# my_board.net
KiCad netlist of a schematic drawn in EAGLE
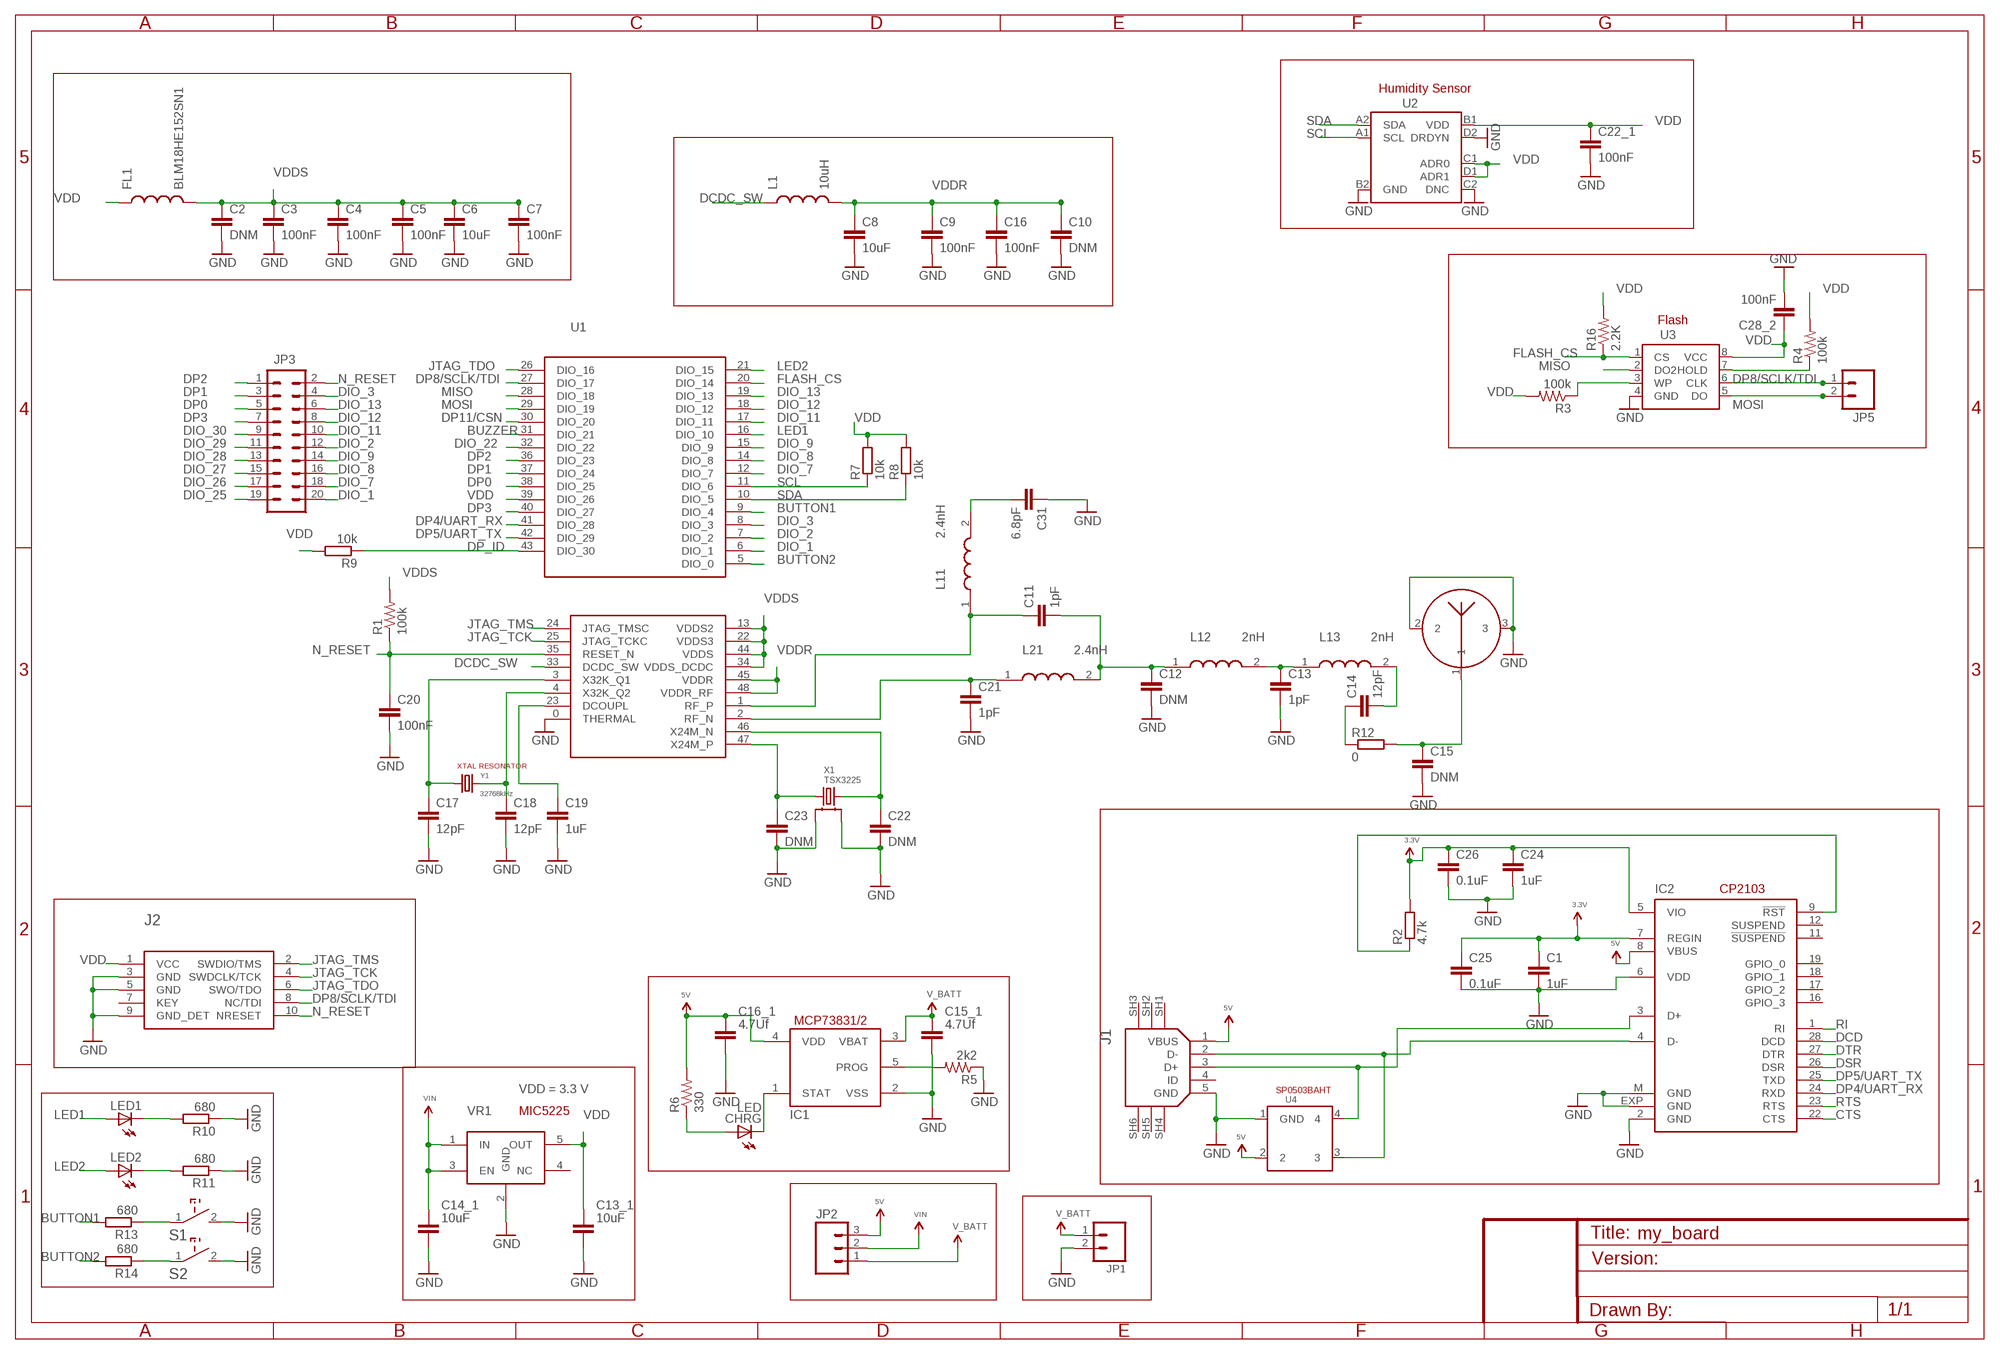
[diagram p0: schematic, sheet 1]

(export (version "E")
  (design (tool "Eeschema 10.0.6"))
  (components
    (comp (ref "C1")
      (value "1uF")
      (footprint "eagle-import:0402-CAP")
      (libsource (lib "eagle-import") (part "SparkFun-Passives_CAP0402-CAP"))
    )
    (comp (ref "C2")
      (value "DNM")
      (footprint "eagle-import:0603-CAP")
      (libsource (lib "eagle-import") (part "CAP0603-CAP"))
    )
    (comp (ref "C3")
      (value "100nF")
      (footprint "eagle-import:0402-CAP")
      (libsource (lib "eagle-import") (part "SparkFun-Passives_CAP0402-CAP"))
    )
    (comp (ref "C4")
      (value "100nF")
      (footprint "eagle-import:0402-CAP")
      (libsource (lib "eagle-import") (part "SparkFun-Passives_CAP0402-CAP"))
    )
    (comp (ref "C5")
      (value "100nF")
      (footprint "eagle-import:0402-CAP")
      (libsource (lib "eagle-import") (part "SparkFun-Passives_CAP0402-CAP"))
    )
    (comp (ref "C6")
      (value "10uF")
      (footprint "eagle-import:0603-CAP")
      (libsource (lib "eagle-import") (part "CAP0603-CAP"))
    )
    (comp (ref "C7")
      (value "100nF")
      (footprint "eagle-import:0603-CAP")
      (libsource (lib "eagle-import") (part "CAP0603-CAP"))
    )
    (comp (ref "C8")
      (value "10uF")
      (footprint "eagle-import:0603-CAP")
      (libsource (lib "eagle-import") (part "CAP0603-CAP"))
    )
    (comp (ref "C9")
      (value "100nF")
      (footprint "eagle-import:0402-CAP")
      (libsource (lib "eagle-import") (part "SparkFun-Passives_CAP0402-CAP"))
    )
    (comp (ref "C10")
      (value "DNM")
      (footprint "eagle-import:0402-CAP")
      (libsource (lib "eagle-import") (part "SparkFun-Passives_CAP0402-CAP"))
    )
    (comp (ref "C11")
      (value "1pF")
      (footprint "eagle-import:0402-CAP")
      (libsource (lib "eagle-import") (part "SparkFun-Passives_CAP0402-CAP"))
    )
    (comp (ref "C12")
      (value "DNM")
      (footprint "eagle-import:0402-CAP")
      (libsource (lib "eagle-import") (part "SparkFun-Passives_CAP0402-CAP"))
    )
    (comp (ref "C13")
      (value "1pF")
      (footprint "eagle-import:0402-CAP")
      (libsource (lib "eagle-import") (part "SparkFun-Passives_CAP0402-CAP"))
    )
    (comp (ref "C13_1")
      (value "10uF")
      (footprint "eagle-import:DP_DEVICES_C603")
      (libsource (lib "eagle-import") (part "DP_DEVICES_CAPACITOR_NPOL-0603"))
    )
    (comp (ref "C14")
      (value "12pF")
      (footprint "eagle-import:0402-CAP")
      (libsource (lib "eagle-import") (part "SparkFun-Passives_CAP0402-CAP"))
    )
    (comp (ref "C14_1")
      (value "10uF")
      (footprint "eagle-import:DP_DEVICES_C603")
      (libsource (lib "eagle-import") (part "DP_DEVICES_CAPACITOR_NPOL-0603"))
    )
    (comp (ref "C15")
      (value "DNM")
      (footprint "eagle-import:0402-CAP")
      (libsource (lib "eagle-import") (part "SparkFun-Passives_CAP0402-CAP"))
    )
    (comp (ref "C15_1")
      (value "4.7Uf")
      (footprint "eagle-import:DP_DEVICES_C603")
      (libsource (lib "eagle-import") (part "DP_DEVICES_CAPACITOR_NPOL-0603"))
    )
    (comp (ref "C16")
      (value "100nF")
      (footprint "eagle-import:0402-CAP")
      (libsource (lib "eagle-import") (part "SparkFun-Passives_CAP0402-CAP"))
    )
    (comp (ref "C16_1")
      (value "4.7Uf")
      (footprint "eagle-import:DP_DEVICES_C603")
      (libsource (lib "eagle-import") (part "DP_DEVICES_CAPACITOR_NPOL-0603"))
    )
    (comp (ref "C17")
      (value "12pF")
      (footprint "eagle-import:0402-CAP")
      (libsource (lib "eagle-import") (part "SparkFun-Passives_CAP0402-CAP"))
    )
    (comp (ref "C18")
      (value "12pF")
      (footprint "eagle-import:0402-CAP")
      (libsource (lib "eagle-import") (part "SparkFun-Passives_CAP0402-CAP"))
    )
    (comp (ref "C19")
      (value "1uF")
      (footprint "eagle-import:0402-CAP")
      (libsource (lib "eagle-import") (part "SparkFun-Passives_CAP0402-CAP"))
    )
    (comp (ref "C20")
      (value "100nF")
      (footprint "eagle-import:0402-CAP")
      (libsource (lib "eagle-import") (part "SparkFun-Passives_CAP0402-CAP"))
    )
    (comp (ref "C21")
      (value "1pF")
      (footprint "eagle-import:0402-CAP")
      (libsource (lib "eagle-import") (part "SparkFun-Passives_CAP0402-CAP"))
    )
    (comp (ref "C22")
      (value "DNM")
      (footprint "eagle-import:0402-CAP")
      (libsource (lib "eagle-import") (part "SparkFun-Passives_CAP0402-CAP"))
    )
    (comp (ref "C22_1")
      (value "100nF")
      (footprint "eagle-import:0402-CAP")
      (libsource (lib "eagle-import") (part "SparkFun-Passives_CAP0402-CAP"))
    )
    (comp (ref "C23")
      (value "DNM")
      (footprint "eagle-import:0402-CAP")
      (libsource (lib "eagle-import") (part "SparkFun-Passives_CAP0402-CAP"))
    )
    (comp (ref "C24")
      (value "1uF")
      (footprint "eagle-import:0402-CAP")
      (libsource (lib "eagle-import") (part "SparkFun-Passives_CAP0402-CAP"))
    )
    (comp (ref "C25")
      (value "0.1uF")
      (footprint "eagle-import:0402-CAP")
      (libsource (lib "eagle-import") (part "SparkFun-Passives_CAP0402-CAP"))
    )
    (comp (ref "C26")
      (value "0.1uF")
      (footprint "eagle-import:0402-CAP")
      (libsource (lib "eagle-import") (part "SparkFun-Passives_CAP0402-CAP"))
    )
    (comp (ref "C28_2")
      (value "100nF")
      (footprint "eagle-import:0402-CAP")
      (libsource (lib "eagle-import") (part "SparkFun-Passives_CAP0402-CAP"))
    )
    (comp (ref "C31")
      (value "6.8pF")
      (footprint "eagle-import:0402-CAP")
      (libsource (lib "eagle-import") (part "SparkFun-Passives_CAP0402-CAP"))
    )
    (comp (ref "CHRG")
      (value "LED")
      (footprint "eagle-import:DP_DEVICES_LED-603")
      (libsource (lib "eagle-import") (part "DP_DEVICES_LED-0603"))
    )
    (comp (ref "FL1")
      (value "BLM18HE152SN1")
      (footprint "eagle-import:0603")
      (libsource (lib "eagle-import") (part "INDUCTOR0603"))
    )
    (comp (ref "IC1")
      (value "ADAFRUIT_MCP73831/OT")
      (footprint "eagle-import:ADAFRUIT_SOT23-5L")
      (libsource (lib "eagle-import") (part "ADAFRUIT_MCP73831/OT"))
    )
    (comp (ref "IC2")
      (value "CP2103_USB_UART")
      (footprint "eagle-import:MLP28")
      (libsource (lib "eagle-import") (part "CP2103_USB_UART"))
    )
    (comp (ref "J1")
      (value "USB-1981568")
      (footprint "eagle-import:1981568-1")
      (libsource (lib "eagle-import") (part "USB-1981568"))
    )
    (comp (ref "J2")
      (value "ARM-10PIN-JTAG")
      (footprint "eagle-import:ARM-10PIN-DEBUGGER")
      (libsource (lib "eagle-import") (part "ARM-10PIN-JTAG"))
    )
    (comp (ref "JP1")
      (value "SPARKFUN-CONNECTORS_M02PTH3")
      (footprint "eagle-import:SPARKFUN-CONNECTORS_1X02_LONGPADS")
      (libsource (lib "eagle-import") (part "SPARKFUN-CONNECTORS_M02PTH3"))
    )
    (comp (ref "JP2")
      (value "M03-SCREW-5MM")
      (footprint "eagle-import:SCREWTERMINAL-5MM-3")
      (libsource (lib "eagle-import") (part "M03-SCREW-5MM"))
    )
    (comp (ref "JP3")
      (value "M10X2")
      (footprint "eagle-import:2X10")
      (libsource (lib "eagle-import") (part "M10X2"))
    )
    (comp (ref "JP5")
      (value "M02PTH")
      (footprint "eagle-import:1X02")
      (libsource (lib "eagle-import") (part "M02PTH"))
    )
    (comp (ref "L1")
      (value "10uH")
      (footprint "eagle-import:0805")
      (libsource (lib "eagle-import") (part "INDUCTOR0805"))
    )
    (comp (ref "L11")
      (value "2.4nH")
      (footprint "eagle-import:LQG15HS2N4S02D")
      (libsource (lib "eagle-import") (part "LQG15HS2N4S02D"))
    )
    (comp (ref "L12")
      (value "2nH")
      (footprint "eagle-import:LQG15HS2N4S02D")
      (libsource (lib "eagle-import") (part "LQG15HS2N4S02D"))
    )
    (comp (ref "L13")
      (value "2nH")
      (footprint "eagle-import:LQG15HS2N4S02D")
      (libsource (lib "eagle-import") (part "LQG15HS2N4S02D"))
    )
    (comp (ref "L21")
      (value "2.4nH")
      (footprint "eagle-import:LQG15HS2N4S02D")
      (libsource (lib "eagle-import") (part "LQG15HS2N4S02D"))
    )
    (comp (ref "LED1")
      (value "DP_DEVICES_LED-0805")
      (footprint "eagle-import:DP_DEVICES_LED-805")
      (libsource (lib "eagle-import") (part "DP_DEVICES_LED-0805"))
    )
    (comp (ref "LED2")
      (value "DP_DEVICES_LED-0805")
      (footprint "eagle-import:DP_DEVICES_LED-805")
      (libsource (lib "eagle-import") (part "DP_DEVICES_LED-0805"))
    )
    (comp (ref "R1")
      (value "100k")
      (footprint "eagle-import:0402-RES")
      (libsource (lib "eagle-import") (part "RESISTOR0402-RES"))
    )
    (comp (ref "R2")
      (value "4.7k")
      (footprint "eagle-import:R0402")
      (libsource (lib "eagle-import") (part "R-EU_R0402"))
    )
    (comp (ref "R3")
      (value "100k")
      (footprint "eagle-import:0402-RES")
      (libsource (lib "eagle-import") (part "RESISTOR0402-RES"))
    )
    (comp (ref "R4")
      (value "100k")
      (footprint "eagle-import:0402-RES")
      (libsource (lib "eagle-import") (part "RESISTOR0402-RES"))
    )
    (comp (ref "R5")
      (value "2k2")
      (footprint "eagle-import:SPARKFUN-RESISTORS_0805")
      (libsource (lib "eagle-import") (part "SPARKFUN-RESISTORS_RESISTOR0805-RES"))
    )
    (comp (ref "R6")
      (value "330")
      (footprint "eagle-import:SPARKFUN-RESISTORS_0805")
      (libsource (lib "eagle-import") (part "SPARKFUN-RESISTORS_RESISTOR0805-RES"))
    )
    (comp (ref "R7")
      (value "10k")
      (footprint "eagle-import:R0402")
      (libsource (lib "eagle-import") (part "R-EU_R0402"))
    )
    (comp (ref "R8")
      (value "10k")
      (footprint "eagle-import:R0402")
      (libsource (lib "eagle-import") (part "R-EU_R0402"))
    )
    (comp (ref "R9")
      (value "10k")
      (footprint "eagle-import:R0402")
      (libsource (lib "eagle-import") (part "R-EU_R0402"))
    )
    (comp (ref "R10")
      (value "680")
      (footprint "eagle-import:R0402")
      (libsource (lib "eagle-import") (part "R-EU_R0402"))
    )
    (comp (ref "R11")
      (value "680")
      (footprint "eagle-import:R0402")
      (libsource (lib "eagle-import") (part "R-EU_R0402"))
    )
    (comp (ref "R12")
      (value "0")
      (footprint "eagle-import:R0402")
      (libsource (lib "eagle-import") (part "R-EU_R0402"))
    )
    (comp (ref "R13")
      (value "680")
      (footprint "eagle-import:R0402")
      (libsource (lib "eagle-import") (part "R-EU_R0402"))
    )
    (comp (ref "R14")
      (value "680")
      (footprint "eagle-import:R0402")
      (libsource (lib "eagle-import") (part "R-EU_R0402"))
    )
    (comp (ref "R16")
      (value "2.2K")
      (footprint "eagle-import:0402-RES")
      (libsource (lib "eagle-import") (part "RESISTOR0402-RES"))
    )
    (comp (ref "S1")
      (value "B3U-1000P-SWITCH")
      (footprint "eagle-import:B3U-1000P-SWITCH")
      (libsource (lib "eagle-import") (part "B3U-1000P-SWITCH"))
    )
    (comp (ref "S2")
      (value "B3U-1000P-SWITCH")
      (footprint "eagle-import:B3U-1000P-SWITCH")
      (libsource (lib "eagle-import") (part "B3U-1000P-SWITCH"))
    )
    (comp (ref "U$1")
      (value "PCB-ANTENNA")
      (footprint "eagle-import:PCB-ANTENNA")
      (libsource (lib "eagle-import") (part "PCB-ANTENNA"))
    )
    (comp (ref "U1")
      (value "CC2650")
      (footprint "eagle-import:CC2650")
      (libsource (lib "eagle-import") (part "CC2650"))
    )
    (comp (ref "U2")
      (value "HDC1000YPA")
      (footprint "eagle-import:HDC1000YPA")
      (libsource (lib "eagle-import") (part "HDC1000YPA"))
    )
    (comp (ref "U3")
      (value "W25X40CLUXIGSS")
      (footprint "eagle-import:W25X40SSIG")
      (libsource (lib "eagle-import") (part "W25X40CLUXIGSS"))
    )
    (comp (ref "U4")
      (value "SP0503BAHT")
      (footprint "eagle-import:SP0503BAHT")
      (libsource (lib "eagle-import") (part "SP0503BAHT"))
    )
    (comp (ref "VR1")
      (value "USBUG_MIC5225-3.3YM5")
      (footprint "eagle-import:USBUG_SOT23-5")
      (fields (field (name "VOLTAGE") "3.3V"))
      (libsource (lib "eagle-import") (part "USBUG_MIC5225YM5-3.3"))
    )
    (comp (ref "X1")
      (value "TSX3225")
      (footprint "eagle-import:TSX-3225")
      (libsource (lib "eagle-import") (part "TSX-3225"))
    )
    (comp (ref "Y1")
      (value "32768kHz")
      (footprint "eagle-import:CRYSTAL_RESONATOR")
      (libsource (lib "eagle-import") (part "CRYSTAL_RESONATOR"))
    )
  )
  (nets
    (net (code "1") (name "/BUTTON1") (class "Default")
      (node (ref "R13") (pin "2") (pinfunction "2_2") (pintype "passive"))
      (node (ref "U1") (pin "9") (pinfunction "DIO_4_9") (pintype "bidirectional"))
    )
    (net (code "2") (name "/BUTTON2") (class "Default")
      (node (ref "R14") (pin "2") (pinfunction "2_2") (pintype "passive"))
      (node (ref "U1") (pin "5") (pinfunction "DIO_0_5") (pintype "bidirectional"))
    )
    (net (code "3") (name "/BUZZER") (class "Default")
      (node (ref "U1") (pin "31") (pinfunction "DIO_21_31") (pintype "bidirectional"))
    )
    (net (code "4") (name "/CTS") (class "Default")
      (node (ref "IC2") (pin "22") (pinfunction "CTS_22") (pintype "input"))
    )
    (net (code "5") (name "/DCD") (class "Default")
      (node (ref "IC2") (pin "28") (pinfunction "DCD_28") (pintype "input"))
    )
    (net (code "6") (name "/DCDC_SW") (class "Default")
      (node (ref "L1") (pin "1") (pinfunction "1_1") (pintype "passive"))
      (node (ref "U1") (pin "33") (pinfunction "DCDC_SW_33") (pintype "power_in"))
    )
    (net (code "7") (name "/DIO_1") (class "Default")
      (node (ref "JP3") (pin "20") (pinfunction "20_20") (pintype "passive"))
      (node (ref "U1") (pin "6") (pinfunction "DIO_1_6") (pintype "bidirectional"))
    )
    (net (code "8") (name "/DIO_2") (class "Default")
      (node (ref "JP3") (pin "12") (pinfunction "12_12") (pintype "passive"))
      (node (ref "U1") (pin "7") (pinfunction "DIO_2_7") (pintype "bidirectional"))
    )
    (net (code "9") (name "/DIO_3") (class "Default")
      (node (ref "JP3") (pin "4") (pinfunction "4_4") (pintype "passive"))
      (node (ref "U1") (pin "8") (pinfunction "DIO_3_8") (pintype "bidirectional"))
    )
    (net (code "10") (name "/DIO_7") (class "Default")
      (node (ref "JP3") (pin "18") (pinfunction "18_18") (pintype "passive"))
      (node (ref "U1") (pin "12") (pinfunction "DIO_7_12") (pintype "bidirectional"))
    )
    (net (code "11") (name "/DIO_8") (class "Default")
      (node (ref "JP3") (pin "16") (pinfunction "16_16") (pintype "passive"))
      (node (ref "U1") (pin "14") (pinfunction "DIO_8_14") (pintype "bidirectional"))
    )
    (net (code "12") (name "/DIO_9") (class "Default")
      (node (ref "JP3") (pin "14") (pinfunction "14_14") (pintype "passive"))
      (node (ref "U1") (pin "15") (pinfunction "DIO_9_15") (pintype "bidirectional"))
    )
    (net (code "13") (name "/DIO_11") (class "Default")
      (node (ref "JP3") (pin "10") (pinfunction "10_10") (pintype "passive"))
      (node (ref "U1") (pin "17") (pinfunction "DIO_11_17") (pintype "bidirectional"))
    )
    (net (code "14") (name "/DIO_12") (class "Default")
      (node (ref "JP3") (pin "8") (pinfunction "8_8") (pintype "passive"))
      (node (ref "U1") (pin "18") (pinfunction "DIO_12_18") (pintype "bidirectional"))
    )
    (net (code "15") (name "/DIO_13") (class "Default")
      (node (ref "JP3") (pin "6") (pinfunction "6_6") (pintype "passive"))
      (node (ref "U1") (pin "19") (pinfunction "DIO_13_19") (pintype "bidirectional"))
    )
    (net (code "16") (name "/DIO_22") (class "Default")
      (node (ref "U1") (pin "32") (pinfunction "DIO_22_32") (pintype "bidirectional"))
    )
    (net (code "17") (name "/DIO_25") (class "Default")
      (node (ref "JP3") (pin "19") (pinfunction "19_19") (pintype "passive"))
    )
    (net (code "18") (name "/DIO_26") (class "Default")
      (node (ref "JP3") (pin "17") (pinfunction "17_17") (pintype "passive"))
    )
    (net (code "19") (name "/DIO_27") (class "Default")
      (node (ref "JP3") (pin "15") (pinfunction "15_15") (pintype "passive"))
    )
    (net (code "20") (name "/DIO_28") (class "Default")
      (node (ref "JP3") (pin "13") (pinfunction "13_13") (pintype "passive"))
    )
    (net (code "21") (name "/DIO_29") (class "Default")
      (node (ref "JP3") (pin "11") (pinfunction "11_11") (pintype "passive"))
    )
    (net (code "22") (name "/DIO_30") (class "Default")
      (node (ref "JP3") (pin "9") (pinfunction "9_9") (pintype "passive"))
    )
    (net (code "23") (name "/DP0") (class "Default")
      (node (ref "JP3") (pin "5") (pinfunction "5_5") (pintype "passive"))
      (node (ref "U1") (pin "38") (pinfunction "DIO_25_38") (pintype "bidirectional"))
    )
    (net (code "24") (name "/DP1") (class "Default")
      (node (ref "JP3") (pin "3") (pinfunction "3_3") (pintype "passive"))
      (node (ref "U1") (pin "37") (pinfunction "DIO_24_37") (pintype "bidirectional"))
    )
    (net (code "25") (name "/DP2") (class "Default")
      (node (ref "JP3") (pin "1") (pinfunction "1_1") (pintype "passive"))
      (node (ref "U1") (pin "36") (pinfunction "DIO_23_36") (pintype "bidirectional"))
    )
    (net (code "26") (name "/DP3") (class "Default")
      (node (ref "JP3") (pin "7") (pinfunction "7_7") (pintype "passive"))
      (node (ref "U1") (pin "40") (pinfunction "DIO_27_40") (pintype "bidirectional"))
    )
    (net (code "27") (name "/DP4{slash}UART_RX") (class "Default")
      (node (ref "IC2") (pin "24") (pinfunction "RXD_24") (pintype "input"))
      (node (ref "U1") (pin "41") (pinfunction "DIO_28_41") (pintype "bidirectional"))
    )
    (net (code "28") (name "/DP5{slash}UART_TX") (class "Default")
      (node (ref "IC2") (pin "25") (pinfunction "TXD_25") (pintype "output"))
      (node (ref "U1") (pin "42") (pinfunction "DIO_29_42") (pintype "bidirectional"))
    )
    (net (code "29") (name "/DP8{slash}SCLK{slash}TDI") (class "Default")
      (node (ref "J2") (pin "8") (pinfunction "NC/TDI_8") (pintype "bidirectional"))
      (node (ref "JP5") (pin "1") (pinfunction "1_1") (pintype "passive"))
      (node (ref "U1") (pin "27") (pinfunction "DIO_17_27") (pintype "bidirectional"))
      (node (ref "U3") (pin "6") (pinfunction "CLK_6") (pintype "input"))
    )
    (net (code "30") (name "/DP11{slash}CSN") (class "Default")
      (node (ref "U1") (pin "30") (pinfunction "DIO_20_30") (pintype "bidirectional"))
    )
    (net (code "31") (name "/DP_ID") (class "Default")
      (node (ref "R9") (pin "1") (pinfunction "1_1") (pintype "passive"))
      (node (ref "U1") (pin "43") (pinfunction "DIO_30_43") (pintype "bidirectional"))
    )
    (net (code "32") (name "/DSR") (class "Default")
      (node (ref "IC2") (pin "26") (pinfunction "DSR_26") (pintype "input"))
    )
    (net (code "33") (name "/DTR") (class "Default")
      (node (ref "IC2") (pin "27") (pinfunction "DTR_27") (pintype "output"))
    )
    (net (code "34") (name "/FLASH_CS") (class "Default")
      (node (ref "R16") (pin "1") (pinfunction "1_1") (pintype "passive"))
      (node (ref "U1") (pin "20") (pinfunction "DIO_14_20") (pintype "bidirectional"))
      (node (ref "U3") (pin "1") (pinfunction "CS_1") (pintype "input"))
    )
    (net (code "35") (name "/JTAG_TCK") (class "Default")
      (node (ref "J2") (pin "4") (pinfunction "SWDCLK/TCK_4") (pintype "bidirectional"))
      (node (ref "U1") (pin "25") (pinfunction "JTAG_TCKC_25") (pintype "bidirectional"))
    )
    (net (code "36") (name "/JTAG_TDO") (class "Default")
      (node (ref "J2") (pin "6") (pinfunction "SWO/TDO_6") (pintype "bidirectional"))
      (node (ref "U1") (pin "26") (pinfunction "DIO_16_26") (pintype "bidirectional"))
    )
    (net (code "37") (name "/JTAG_TMS") (class "Default")
      (node (ref "J2") (pin "2") (pinfunction "SWDIO/TMS_2") (pintype "bidirectional"))
      (node (ref "U1") (pin "24") (pinfunction "JTAG_TMSC_24") (pintype "bidirectional"))
    )
    (net (code "38") (name "/LED1") (class "Default")
      (node (ref "LED1") (pin "A") (pinfunction "A_A") (pintype "passive"))
      (node (ref "U1") (pin "16") (pinfunction "DIO_10_16") (pintype "bidirectional"))
    )
    (net (code "39") (name "/LED2") (class "Default")
      (node (ref "LED2") (pin "A") (pinfunction "A_A") (pintype "passive"))
      (node (ref "U1") (pin "21") (pinfunction "DIO_15_21") (pintype "bidirectional"))
    )
    (net (code "40") (name "/MISO") (class "Default")
      (node (ref "U1") (pin "28") (pinfunction "DIO_18_28") (pintype "bidirectional"))
      (node (ref "U3") (pin "2") (pinfunction "DO2_2") (pintype "bidirectional"))
    )
    (net (code "41") (name "/MOSI") (class "Default")
      (node (ref "JP5") (pin "2") (pinfunction "2_2") (pintype "passive"))
      (node (ref "U1") (pin "29") (pinfunction "DIO_19_29") (pintype "bidirectional"))
      (node (ref "U3") (pin "5") (pinfunction "DO_5") (pintype "bidirectional"))
    )
    (net (code "42") (name "/N_RESET") (class "Default")
      (node (ref "C20") (pin "1") (pinfunction "1_1") (pintype "passive"))
      (node (ref "J2") (pin "10") (pinfunction "NRESET_10") (pintype "bidirectional"))
      (node (ref "JP3") (pin "2") (pinfunction "2_2") (pintype "passive"))
      (node (ref "R1") (pin "1") (pinfunction "1_1") (pintype "passive"))
      (node (ref "U1") (pin "35") (pinfunction "RESET_N_35") (pintype "input"))
    )
    (net (code "43") (name "/RI") (class "Default")
      (node (ref "IC2") (pin "1") (pinfunction "RI_1") (pintype "input"))
    )
    (net (code "44") (name "/RTS") (class "Default")
      (node (ref "IC2") (pin "23") (pinfunction "RTS_23") (pintype "output"))
    )
    (net (code "45") (name "/SCL") (class "Default")
      (node (ref "R7") (pin "1") (pinfunction "1_1") (pintype "passive"))
      (node (ref "U1") (pin "11") (pinfunction "DIO_6_11") (pintype "bidirectional"))
      (node (ref "U2") (pin "A1") (pinfunction "SCL_A1") (pintype "input"))
    )
    (net (code "46") (name "/SDA") (class "Default")
      (node (ref "R8") (pin "1") (pinfunction "1_1") (pintype "passive"))
      (node (ref "U1") (pin "10") (pinfunction "DIO_5_10") (pintype "bidirectional"))
      (node (ref "U2") (pin "A2") (pinfunction "SDA_A2") (pintype "bidirectional"))
    )
    (net (code "47") (name "/VDD") (class "Default")
      (node (ref "C13_1") (pin "1") (pinfunction "1_1") (pintype "passive"))
      (node (ref "C22_1") (pin "1") (pinfunction "1_1") (pintype "passive"))
      (node (ref "C28_2") (pin "1") (pinfunction "1_1") (pintype "passive"))
      (node (ref "FL1") (pin "1") (pinfunction "1_1") (pintype "passive"))
      (node (ref "J2") (pin "1") (pinfunction "VCC_1") (pintype "bidirectional"))
      (node (ref "R16") (pin "2") (pinfunction "2_2") (pintype "passive"))
      (node (ref "R3") (pin "2") (pinfunction "2_2") (pintype "passive"))
      (node (ref "R4") (pin "2") (pinfunction "2_2") (pintype "passive"))
      (node (ref "R7") (pin "2") (pinfunction "2_2") (pintype "passive"))
      (node (ref "R8") (pin "2") (pinfunction "2_2") (pintype "passive"))
      (node (ref "R9") (pin "2") (pinfunction "2_2") (pintype "passive"))
      (node (ref "U1") (pin "39") (pinfunction "DIO_26_39") (pintype "bidirectional"))
      (node (ref "U2") (pin "B1") (pinfunction "VDD_B1") (pintype "power_in"))
      (node (ref "U2") (pin "C1") (pinfunction "ADR0_C1") (pintype "input"))
      (node (ref "U2") (pin "D1") (pinfunction "ADR1_D1") (pintype "input"))
      (node (ref "U3") (pin "8") (pinfunction "VCC_8") (pintype "power_in"))
      (node (ref "VR1") (pin "5") (pinfunction "OUT_5") (pintype "passive"))
    )
    (net (code "48") (name "/VDDR") (class "Default")
      (node (ref "C10") (pin "1") (pinfunction "1_1") (pintype "passive"))
      (node (ref "C16") (pin "1") (pinfunction "1_1") (pintype "passive"))
      (node (ref "C8") (pin "1") (pinfunction "1_1") (pintype "passive"))
      (node (ref "C9") (pin "1") (pinfunction "1_1") (pintype "passive"))
      (node (ref "L1") (pin "2") (pinfunction "2_2") (pintype "passive"))
      (node (ref "U1") (pin "45") (pinfunction "VDDR_45") (pintype "power_in"))
      (node (ref "U1") (pin "48") (pinfunction "VDDR_RF_48") (pintype "power_in"))
    )
    (net (code "49") (name "/VDDS") (class "Default")
      (node (ref "C2") (pin "1") (pinfunction "1_1") (pintype "passive"))
      (node (ref "C3") (pin "1") (pinfunction "1_1") (pintype "passive"))
      (node (ref "C4") (pin "1") (pinfunction "1_1") (pintype "passive"))
      (node (ref "C5") (pin "1") (pinfunction "1_1") (pintype "passive"))
      (node (ref "C6") (pin "1") (pinfunction "1_1") (pintype "passive"))
      (node (ref "C7") (pin "1") (pinfunction "1_1") (pintype "passive"))
      (node (ref "FL1") (pin "2") (pinfunction "2_2") (pintype "passive"))
      (node (ref "R1") (pin "2") (pinfunction "2_2") (pintype "passive"))
      (node (ref "U1") (pin "13") (pinfunction "VDDS2_13") (pintype "power_in"))
      (node (ref "U1") (pin "22") (pinfunction "VDDS3_22") (pintype "power_in"))
      (node (ref "U1") (pin "34") (pinfunction "VDDS_DCDC_34") (pintype "power_in"))
      (node (ref "U1") (pin "44") (pinfunction "VDDS_44") (pintype "power_in"))
    )
    (net (code "50") (name "3.3V") (class "Default")
      (node (ref "C1") (pin "1") (pinfunction "1_1") (pintype "passive"))
      (node (ref "C24") (pin "1") (pinfunction "1_1") (pintype "passive"))
      (node (ref "C25") (pin "1") (pinfunction "1_1") (pintype "passive"))
      (node (ref "C26") (pin "1") (pinfunction "1_1") (pintype "passive"))
      (node (ref "IC2") (pin "5") (pinfunction "VIO_5") (pintype "power_in"))
      (node (ref "IC2") (pin "7") (pinfunction "REGIN_7") (pintype "passive"))
      (node (ref "R2") (pin "2") (pinfunction "2_2") (pintype "passive"))
    )
    (net (code "51") (name "5V") (class "Default")
      (node (ref "C16_1") (pin "1") (pinfunction "1_1") (pintype "passive"))
      (node (ref "IC1") (pin "4") (pinfunction "VDD_4") (pintype "power_in"))
      (node (ref "IC2") (pin "8") (pinfunction "VBUS_8") (pintype "input"))
      (node (ref "J1") (pin "1") (pinfunction "VBUS_1") (pintype "bidirectional"))
      (node (ref "JP2") (pin "3") (pinfunction "3_3") (pintype "passive"))
      (node (ref "R6") (pin "2") (pinfunction "2_2") (pintype "passive"))
      (node (ref "U4") (pin "2") (pinfunction "2_2") (pintype "bidirectional"))
    )
    (net (code "52") (name "GND") (class "Default")
      (node (ref "C1") (pin "2") (pinfunction "2_2") (pintype "passive"))
      (node (ref "C10") (pin "2") (pinfunction "2_2") (pintype "passive"))
      (node (ref "C12") (pin "2") (pinfunction "2_2") (pintype "passive"))
      (node (ref "C13") (pin "2") (pinfunction "2_2") (pintype "passive"))
      (node (ref "C13_1") (pin "2") (pinfunction "2_2") (pintype "passive"))
      (node (ref "C14_1") (pin "2") (pinfunction "2_2") (pintype "passive"))
      (node (ref "C15") (pin "2") (pinfunction "2_2") (pintype "passive"))
      (node (ref "C15_1") (pin "2") (pinfunction "2_2") (pintype "passive"))
      (node (ref "C16") (pin "2") (pinfunction "2_2") (pintype "passive"))
      (node (ref "C16_1") (pin "2") (pinfunction "2_2") (pintype "passive"))
      (node (ref "C17") (pin "2") (pinfunction "2_2") (pintype "passive"))
      (node (ref "C18") (pin "2") (pinfunction "2_2") (pintype "passive"))
      (node (ref "C19") (pin "2") (pinfunction "2_2") (pintype "passive"))
      (node (ref "C2") (pin "2") (pinfunction "2_2") (pintype "passive"))
      (node (ref "C20") (pin "2") (pinfunction "2_2") (pintype "passive"))
      (node (ref "C21") (pin "2") (pinfunction "2_2") (pintype "passive"))
      (node (ref "C22") (pin "2") (pinfunction "2_2") (pintype "passive"))
      (node (ref "C22_1") (pin "2") (pinfunction "2_2") (pintype "passive"))
      (node (ref "C23") (pin "2") (pinfunction "2_2") (pintype "passive"))
      (node (ref "C24") (pin "2") (pinfunction "2_2") (pintype "passive"))
      (node (ref "C25") (pin "2") (pinfunction "2_2") (pintype "passive"))
      (node (ref "C26") (pin "2") (pinfunction "2_2") (pintype "passive"))
      (node (ref "C28_2") (pin "2") (pinfunction "2_2") (pintype "passive"))
      (node (ref "C3") (pin "2") (pinfunction "2_2") (pintype "passive"))
      (node (ref "C31") (pin "1") (pinfunction "1_1") (pintype "passive"))
      (node (ref "C4") (pin "2") (pinfunction "2_2") (pintype "passive"))
      (node (ref "C5") (pin "2") (pinfunction "2_2") (pintype "passive"))
      (node (ref "C6") (pin "2") (pinfunction "2_2") (pintype "passive"))
      (node (ref "C7") (pin "2") (pinfunction "2_2") (pintype "passive"))
      (node (ref "C8") (pin "2") (pinfunction "2_2") (pintype "passive"))
      (node (ref "C9") (pin "2") (pinfunction "2_2") (pintype "passive"))
      (node (ref "IC1") (pin "2") (pinfunction "VSS_2") (pintype "power_in"))
      (node (ref "IC2") (pin "2") (pinfunction "GND_2") (pintype "power_in"))
      (node (ref "IC2") (pin "6") (pinfunction "VDD_6") (pintype "power_in"))
      (node (ref "IC2") (pin "EXP") (pinfunction "GND_EXP") (pintype "power_in"))
      (node (ref "IC2") (pin "M") (pinfunction "GND_M") (pintype "power_in"))
      (node (ref "J1") (pin "5") (pinfunction "GND_5") (pintype "bidirectional"))
      (node (ref "J2") (pin "3") (pinfunction "GND_3") (pintype "bidirectional"))
      (node (ref "J2") (pin "5") (pinfunction "GND_5") (pintype "bidirectional"))
      (node (ref "J2") (pin "9") (pinfunction "GND_DET_9") (pintype "bidirectional"))
      (node (ref "JP1") (pin "2") (pinfunction "2_2") (pintype "passive"))
      (node (ref "R10") (pin "1") (pinfunction "1_1") (pintype "passive"))
      (node (ref "R11") (pin "1") (pinfunction "1_1") (pintype "passive"))
      (node (ref "R5") (pin "1") (pinfunction "1_1") (pintype "passive"))
      (node (ref "S1") (pin "2") (pinfunction "2_2") (pintype "bidirectional"))
      (node (ref "S2") (pin "2") (pinfunction "2_2") (pintype "bidirectional"))
      (node (ref "U$1") (pin "2") (pinfunction "2_2") (pintype "bidirectional"))
      (node (ref "U$1") (pin "3") (pinfunction "3_3") (pintype "bidirectional"))
      (node (ref "U1") (pin "0") (pinfunction "THERMAL_0") (pintype "bidirectional"))
      (node (ref "U2") (pin "B2") (pinfunction "GND_B2") (pintype "power_in"))
      (node (ref "U2") (pin "C2") (pinfunction "DNC_C2") (pintype "power_in"))
      (node (ref "U2") (pin "D2") (pinfunction "DRDYN_D2") (pintype "bidirectional"))
      (node (ref "U3") (pin "4") (pinfunction "GND_4") (pintype "power_in"))
      (node (ref "U4") (pin "1") (pinfunction "GND_1") (pintype "power_in"))
      (node (ref "VR1") (pin "2") (pinfunction "GND_2") (pintype "passive"))
      (node (ref "X1") (pin "2") (pinfunction "2_2") (pintype "power_in"))
      (node (ref "X1") (pin "4") (pinfunction "4_4") (pintype "power_in"))
    )
    (net (code "53") (name "Net-(C14-Pad1)") (class "Default")
      (node (ref "C14") (pin "1") (pinfunction "1_1") (pintype "passive"))
      (node (ref "R12") (pin "1") (pinfunction "1_1") (pintype "passive"))
    )
    (net (code "54") (name "Net-(C15-Pad1)") (class "Default")
      (node (ref "C15") (pin "1") (pinfunction "1_1") (pintype "passive"))
      (node (ref "R12") (pin "2") (pinfunction "2_2") (pintype "passive"))
      (node (ref "U$1") (pin "1") (pinfunction "1_1") (pintype "bidirectional"))
    )
    (net (code "55") (name "Net-(CHRG-PadA)") (class "Default")
      (node (ref "CHRG") (pin "A") (pinfunction "A_A") (pintype "passive"))
      (node (ref "R6") (pin "1") (pinfunction "1_1") (pintype "passive"))
    )
    (net (code "56") (name "Net-(IC1-PROG)") (class "Default")
      (node (ref "IC1") (pin "5") (pinfunction "PROG_5") (pintype "input"))
      (node (ref "R5") (pin "2") (pinfunction "2_2") (pintype "passive"))
    )
    (net (code "57") (name "Net-(IC1-STAT)") (class "Default")
      (node (ref "CHRG") (pin "C") (pinfunction "C_C") (pintype "passive"))
      (node (ref "IC1") (pin "1") (pinfunction "STAT_1") (pintype "output"))
    )
    (net (code "58") (name "Net-(IC2-D+)") (class "Default")
      (node (ref "IC2") (pin "3") (pinfunction "D+_3") (pintype "bidirectional"))
      (node (ref "J1") (pin "3") (pinfunction "D+_3") (pintype "bidirectional"))
      (node (ref "U4") (pin "4") (pinfunction "4_4") (pintype "bidirectional"))
    )
    (net (code "59") (name "Net-(IC2-D-)") (class "Default")
      (node (ref "IC2") (pin "4") (pinfunction "D-_4") (pintype "bidirectional"))
      (node (ref "J1") (pin "2") (pinfunction "D-_2") (pintype "bidirectional"))
      (node (ref "U4") (pin "3") (pinfunction "3_3") (pintype "bidirectional"))
    )
    (net (code "60") (name "Net-(IC2-~{RST})") (class "Default")
      (node (ref "IC2") (pin "9") (pinfunction "~{RST}_9") (pintype "bidirectional"))
      (node (ref "R2") (pin "1") (pinfunction "1_1") (pintype "passive"))
    )
    (net (code "61") (name "Net-(L11-P$1)") (class "Default")
      (node (ref "C11") (pin "1") (pinfunction "1_1") (pintype "passive"))
      (node (ref "L11") (pin "1") (pinfunction "P$1_1") (pintype "bidirectional"))
      (node (ref "U1") (pin "1") (pinfunction "RF_P_1") (pintype "bidirectional"))
    )
    (net (code "62") (name "Net-(L11-P$2)") (class "Default")
      (node (ref "C31") (pin "2") (pinfunction "2_2") (pintype "passive"))
      (node (ref "L11") (pin "2") (pinfunction "P$2_2") (pintype "bidirectional"))
    )
    (net (code "63") (name "Net-(L12-P$1)") (class "Default")
      (node (ref "C11") (pin "2") (pinfunction "2_2") (pintype "passive"))
      (node (ref "C12") (pin "1") (pinfunction "1_1") (pintype "passive"))
      (node (ref "L12") (pin "1") (pinfunction "P$1_1") (pintype "bidirectional"))
      (node (ref "L21") (pin "2") (pinfunction "P$2_2") (pintype "bidirectional"))
    )
    (net (code "64") (name "Net-(L12-P$2)") (class "Default")
      (node (ref "C13") (pin "1") (pinfunction "1_1") (pintype "passive"))
      (node (ref "L12") (pin "2") (pinfunction "P$2_2") (pintype "bidirectional"))
      (node (ref "L13") (pin "1") (pinfunction "P$1_1") (pintype "bidirectional"))
    )
    (net (code "65") (name "Net-(L13-P$2)") (class "Default")
      (node (ref "C14") (pin "2") (pinfunction "2_2") (pintype "passive"))
      (node (ref "L13") (pin "2") (pinfunction "P$2_2") (pintype "bidirectional"))
    )
    (net (code "66") (name "Net-(L21-P$1)") (class "Default")
      (node (ref "C21") (pin "1") (pinfunction "1_1") (pintype "passive"))
      (node (ref "L21") (pin "1") (pinfunction "P$1_1") (pintype "bidirectional"))
      (node (ref "U1") (pin "2") (pinfunction "RF_N_2") (pintype "bidirectional"))
    )
    (net (code "67") (name "Net-(LED1-PadC)") (class "Default")
      (node (ref "LED1") (pin "C") (pinfunction "C_C") (pintype "passive"))
      (node (ref "R10") (pin "2") (pinfunction "2_2") (pintype "passive"))
    )
    (net (code "68") (name "Net-(LED2-PadC)") (class "Default")
      (node (ref "LED2") (pin "C") (pinfunction "C_C") (pintype "passive"))
      (node (ref "R11") (pin "2") (pinfunction "2_2") (pintype "passive"))
    )
    (net (code "69") (name "Net-(R13-Pad1)") (class "Default")
      (node (ref "R13") (pin "1") (pinfunction "1_1") (pintype "passive"))
      (node (ref "S1") (pin "1") (pinfunction "1_1") (pintype "bidirectional"))
    )
    (net (code "70") (name "Net-(R14-Pad1)") (class "Default")
      (node (ref "R14") (pin "1") (pinfunction "1_1") (pintype "passive"))
      (node (ref "S2") (pin "1") (pinfunction "1_1") (pintype "bidirectional"))
    )
    (net (code "71") (name "Net-(U1-DCOUPL)") (class "Default")
      (node (ref "C19") (pin "1") (pinfunction "1_1") (pintype "passive"))
      (node (ref "U1") (pin "23") (pinfunction "DCOUPL_23") (pintype "power_in"))
    )
    (net (code "72") (name "Net-(U1-X24M_N)") (class "Default")
      (node (ref "C22") (pin "1") (pinfunction "1_1") (pintype "passive"))
      (node (ref "U1") (pin "46") (pinfunction "X24M_N_46") (pintype "bidirectional"))
      (node (ref "X1") (pin "3") (pinfunction "3_3") (pintype "bidirectional"))
    )
    (net (code "73") (name "Net-(U1-X24M_P)") (class "Default")
      (node (ref "C23") (pin "1") (pinfunction "1_1") (pintype "passive"))
      (node (ref "U1") (pin "47") (pinfunction "X24M_P_47") (pintype "bidirectional"))
      (node (ref "X1") (pin "1") (pinfunction "1_1") (pintype "bidirectional"))
    )
    (net (code "74") (name "Net-(U1-X32K_Q1)") (class "Default")
      (node (ref "C17") (pin "1") (pinfunction "1_1") (pintype "passive"))
      (node (ref "U1") (pin "3") (pinfunction "X32K_Q1_3") (pintype "bidirectional"))
      (node (ref "Y1") (pin "P$1") (pinfunction "1_P$1") (pintype "passive"))
    )
    (net (code "75") (name "Net-(U1-X32K_Q2)") (class "Default")
      (node (ref "C18") (pin "1") (pinfunction "1_1") (pintype "passive"))
      (node (ref "U1") (pin "4") (pinfunction "X32K_Q2_4") (pintype "bidirectional"))
      (node (ref "Y1") (pin "P$4") (pinfunction "2_P$4") (pintype "passive"))
    )
    (net (code "76") (name "Net-(U3-HOLD)") (class "Default")
      (node (ref "R4") (pin "1") (pinfunction "1_1") (pintype "passive"))
      (node (ref "U3") (pin "7") (pinfunction "HOLD_7") (pintype "input"))
    )
    (net (code "77") (name "Net-(U3-WP)") (class "Default")
      (node (ref "R3") (pin "1") (pinfunction "1_1") (pintype "passive"))
      (node (ref "U3") (pin "3") (pinfunction "WP_3") (pintype "input"))
    )
    (net (code "78") (name "VIN") (class "Default")
      (node (ref "C14_1") (pin "1") (pinfunction "1_1") (pintype "passive"))
      (node (ref "JP2") (pin "2") (pinfunction "2_2") (pintype "passive"))
      (node (ref "VR1") (pin "1") (pinfunction "IN_1") (pintype "passive"))
      (node (ref "VR1") (pin "3") (pinfunction "EN_3") (pintype "input"))
    )
    (net (code "79") (name "V_BATT") (class "Default")
      (node (ref "C15_1") (pin "1") (pinfunction "1_1") (pintype "passive"))
      (node (ref "IC1") (pin "3") (pinfunction "VBAT_3") (pintype "bidirectional"))
      (node (ref "JP1") (pin "1") (pinfunction "1_1") (pintype "passive"))
      (node (ref "JP2") (pin "1") (pinfunction "1_1") (pintype "passive"))
    )
    (net (code "80") (name "unconnected-(IC2-GPIO_0-Pad19)") (class "Default")
      (node (ref "IC2") (pin "19") (pinfunction "GPIO_0_19") (pintype "bidirectional"))
    )
    (net (code "81") (name "unconnected-(IC2-GPIO_1-Pad18)") (class "Default")
      (node (ref "IC2") (pin "18") (pinfunction "GPIO_1_18") (pintype "bidirectional"))
    )
    (net (code "82") (name "unconnected-(IC2-GPIO_2-Pad17)") (class "Default")
      (node (ref "IC2") (pin "17") (pinfunction "GPIO_2_17") (pintype "bidirectional"))
    )
    (net (code "83") (name "unconnected-(IC2-GPIO_3-Pad16)") (class "Default")
      (node (ref "IC2") (pin "16") (pinfunction "GPIO_3_16") (pintype "bidirectional"))
    )
    (net (code "84") (name "unconnected-(IC2-SUSPEND-Pad12)") (class "Default")
      (node (ref "IC2") (pin "12") (pinfunction "SUSPEND_12") (pintype "output"))
    )
    (net (code "85") (name "unconnected-(IC2-~{SUSPEND}-Pad11)") (class "Default")
      (node (ref "IC2") (pin "11") (pinfunction "~{SUSPEND}_11") (pintype "output"))
    )
    (net (code "86") (name "unconnected-(J1-ID-Pad4)") (class "Default")
      (node (ref "J1") (pin "4") (pinfunction "ID_4") (pintype "bidirectional"))
    )
    (net (code "87") (name "unconnected-(J1-P$1-PadSH1)") (class "Default")
      (node (ref "J1") (pin "SH1") (pinfunction "P$1_SH1") (pintype "bidirectional"))
    )
    (net (code "88") (name "unconnected-(J1-P$2-PadSH2)") (class "Default")
      (node (ref "J1") (pin "SH2") (pinfunction "P$2_SH2") (pintype "bidirectional"))
    )
    (net (code "89") (name "unconnected-(J1-P$3-PadSH3)") (class "Default")
      (node (ref "J1") (pin "SH3") (pinfunction "P$3_SH3") (pintype "bidirectional"))
    )
    (net (code "90") (name "unconnected-(J1-P$4-PadSH4)") (class "Default")
      (node (ref "J1") (pin "SH4") (pinfunction "P$4_SH4") (pintype "bidirectional"))
    )
    (net (code "91") (name "unconnected-(J1-P$5-PadSH5)") (class "Default")
      (node (ref "J1") (pin "SH5") (pinfunction "P$5_SH5") (pintype "bidirectional"))
    )
    (net (code "92") (name "unconnected-(J1-P$6-PadSH6)") (class "Default")
      (node (ref "J1") (pin "SH6") (pinfunction "P$6_SH6") (pintype "bidirectional"))
    )
    (net (code "93") (name "unconnected-(J2-KEY-Pad7)") (class "Default")
      (node (ref "J2") (pin "7") (pinfunction "KEY_7") (pintype "bidirectional"))
    )
    (net (code "94") (name "unconnected-(VR1-NC-Pad4)") (class "Default")
      (node (ref "VR1") (pin "4") (pinfunction "NC_4") (pintype "no_connect"))
    )
  )
)
